# Arduino_Clock_Dividerx4_board2.net
KiCad netlist of a schematic drawn in EAGLE
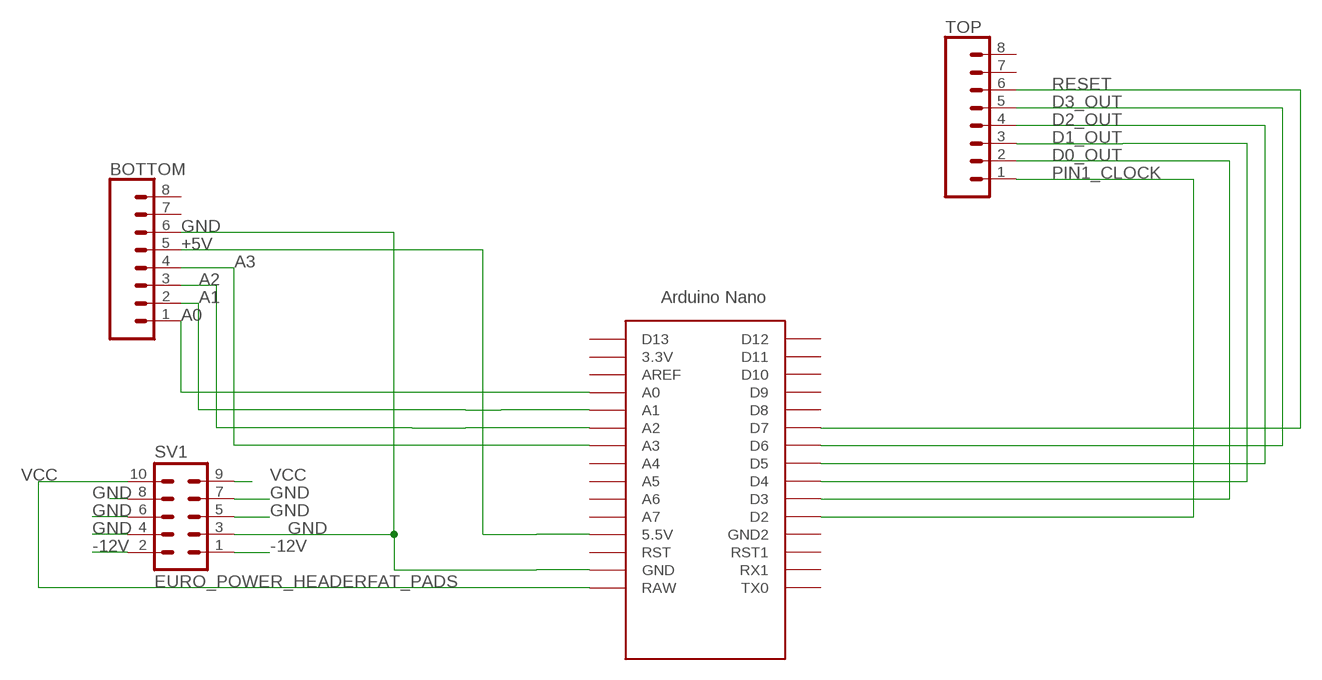
[diagram p0: schematic, sheet 1]

(export (version "E")
  (design (tool "Eeschema 10.0.6"))
  (components
    (comp (ref "BOTTOM")
      (value "CONN_08LONGPADS")
      (footprint "eagle-import:1X08_LONGPADS")
      (libsource (lib "eagle-import") (part "CONN_08LONGPADS"))
    )
    (comp (ref "SV1")
      (value "EURO_POWER_HEADERFAT_PADS")
      (footprint "eagle-import:EURO_PWR_HEADER_FAT")
      (libsource (lib "eagle-import") (part "EURO_POWER_HEADERFAT_PADS"))
    )
    (comp (ref "TOP")
      (value "CONN_08LONGPADS")
      (footprint "eagle-import:1X08_LONGPADS")
      (libsource (lib "eagle-import") (part "CONN_08LONGPADS"))
    )
    (comp (ref "U$1")
      (value "NANO")
      (footprint "eagle-import:NANO")
      (libsource (lib "eagle-import") (part "NANO"))
    )
  )
  (nets
    (net (code "1") (name "/+5V") (class "Default")
      (node (ref "BOTTOM") (pin "5") (pinfunction "5_5") (pintype "passive"))
      (node (ref "U$1") (pin "5V") (pinfunction "5.5V_5V") (pintype "bidirectional"))
    )
    (net (code "2") (name "/-12V") (class "Default")
      (node (ref "SV1") (pin "1") (pinfunction "1_1") (pintype "passive"))
      (node (ref "SV1") (pin "2") (pinfunction "2_2") (pintype "passive"))
    )
    (net (code "3") (name "/A0") (class "Default")
      (node (ref "BOTTOM") (pin "1") (pinfunction "1_1") (pintype "passive"))
      (node (ref "U$1") (pin "A0") (pinfunction "A0_A0") (pintype "bidirectional"))
    )
    (net (code "4") (name "/A1") (class "Default")
      (node (ref "BOTTOM") (pin "2") (pinfunction "2_2") (pintype "passive"))
      (node (ref "U$1") (pin "A1") (pinfunction "A1_A1") (pintype "bidirectional"))
    )
    (net (code "5") (name "/A2") (class "Default")
      (node (ref "BOTTOM") (pin "3") (pinfunction "3_3") (pintype "passive"))
      (node (ref "U$1") (pin "A2") (pinfunction "A2_A2") (pintype "bidirectional"))
    )
    (net (code "6") (name "/A3") (class "Default")
      (node (ref "BOTTOM") (pin "4") (pinfunction "4_4") (pintype "passive"))
      (node (ref "U$1") (pin "A3") (pinfunction "A3_A3") (pintype "bidirectional"))
    )
    (net (code "7") (name "/D0_OUT") (class "Default")
      (node (ref "TOP") (pin "2") (pinfunction "2_2") (pintype "passive"))
      (node (ref "U$1") (pin "D3") (pinfunction "D3_D3") (pintype "bidirectional"))
    )
    (net (code "8") (name "/D1_OUT") (class "Default")
      (node (ref "TOP") (pin "3") (pinfunction "3_3") (pintype "passive"))
      (node (ref "U$1") (pin "D4") (pinfunction "D4_D4") (pintype "bidirectional"))
    )
    (net (code "9") (name "/D2_OUT") (class "Default")
      (node (ref "TOP") (pin "4") (pinfunction "4_4") (pintype "passive"))
      (node (ref "U$1") (pin "D5") (pinfunction "D5_D5") (pintype "bidirectional"))
    )
    (net (code "10") (name "/D3_OUT") (class "Default")
      (node (ref "TOP") (pin "5") (pinfunction "5_5") (pintype "passive"))
      (node (ref "U$1") (pin "D6") (pinfunction "D6_D6") (pintype "bidirectional"))
    )
    (net (code "11") (name "/GND") (class "Default")
      (node (ref "BOTTOM") (pin "6") (pinfunction "6_6") (pintype "passive"))
      (node (ref "SV1") (pin "3") (pinfunction "3_3") (pintype "passive"))
      (node (ref "SV1") (pin "4") (pinfunction "4_4") (pintype "passive"))
      (node (ref "SV1") (pin "5") (pinfunction "5_5") (pintype "passive"))
      (node (ref "SV1") (pin "6") (pinfunction "6_6") (pintype "passive"))
      (node (ref "SV1") (pin "7") (pinfunction "7_7") (pintype "passive"))
      (node (ref "SV1") (pin "8") (pinfunction "8_8") (pintype "passive"))
      (node (ref "U$1") (pin "GND") (pinfunction "GND_GND") (pintype "bidirectional"))
    )
    (net (code "12") (name "/PIN1_CLOCK") (class "Default")
      (node (ref "TOP") (pin "1") (pinfunction "1_1") (pintype "passive"))
      (node (ref "U$1") (pin "D2") (pinfunction "D2_D2") (pintype "bidirectional"))
    )
    (net (code "13") (name "/RESET") (class "Default")
      (node (ref "TOP") (pin "6") (pinfunction "6_6") (pintype "passive"))
      (node (ref "U$1") (pin "D7") (pinfunction "D7_D7") (pintype "bidirectional"))
    )
    (net (code "14") (name "/VCC") (class "Default")
      (node (ref "SV1") (pin "10") (pinfunction "10_10") (pintype "passive"))
      (node (ref "SV1") (pin "9") (pinfunction "9_9") (pintype "passive"))
      (node (ref "U$1") (pin "RAW") (pinfunction "RAW_RAW") (pintype "bidirectional"))
    )
    (net (code "15") (name "unconnected-(BOTTOM-Pad7)") (class "Default")
      (node (ref "BOTTOM") (pin "7") (pinfunction "7_7") (pintype "passive"))
    )
    (net (code "16") (name "unconnected-(BOTTOM-Pad8)") (class "Default")
      (node (ref "BOTTOM") (pin "8") (pinfunction "8_8") (pintype "passive"))
    )
    (net (code "17") (name "unconnected-(TOP-Pad7)") (class "Default")
      (node (ref "TOP") (pin "7") (pinfunction "7_7") (pintype "passive"))
    )
    (net (code "18") (name "unconnected-(TOP-Pad8)") (class "Default")
      (node (ref "TOP") (pin "8") (pinfunction "8_8") (pintype "passive"))
    )
    (net (code "19") (name "unconnected-(U$1-GND2-PadGND1)") (class "Default")
      (node (ref "U$1") (pin "GND1") (pinfunction "GND2_GND1") (pintype "bidirectional"))
    )
    (net (code "20") (name "unconnected-(U$1-Pad3.3V)") (class "Default")
      (node (ref "U$1") (pin "3.3V") (pinfunction "3.3V_3.3V") (pintype "bidirectional"))
    )
    (net (code "21") (name "unconnected-(U$1-PadA4)") (class "Default")
      (node (ref "U$1") (pin "A4") (pinfunction "A4_A4") (pintype "bidirectional"))
    )
    (net (code "22") (name "unconnected-(U$1-PadA5)") (class "Default")
      (node (ref "U$1") (pin "A5") (pinfunction "A5_A5") (pintype "bidirectional"))
    )
    (net (code "23") (name "unconnected-(U$1-PadA6)") (class "Default")
      (node (ref "U$1") (pin "A6") (pinfunction "A6_A6") (pintype "bidirectional"))
    )
    (net (code "24") (name "unconnected-(U$1-PadA7)") (class "Default")
      (node (ref "U$1") (pin "A7") (pinfunction "A7_A7") (pintype "bidirectional"))
    )
    (net (code "25") (name "unconnected-(U$1-PadAREF)") (class "Default")
      (node (ref "U$1") (pin "AREF") (pinfunction "AREF_AREF") (pintype "bidirectional"))
    )
    (net (code "26") (name "unconnected-(U$1-PadD8)") (class "Default")
      (node (ref "U$1") (pin "D8") (pinfunction "D8_D8") (pintype "bidirectional"))
    )
    (net (code "27") (name "unconnected-(U$1-PadD9)") (class "Default")
      (node (ref "U$1") (pin "D9") (pinfunction "D9_D9") (pintype "bidirectional"))
    )
    (net (code "28") (name "unconnected-(U$1-PadD10)") (class "Default")
      (node (ref "U$1") (pin "D10") (pinfunction "D10_D10") (pintype "bidirectional"))
    )
    (net (code "29") (name "unconnected-(U$1-PadD11)") (class "Default")
      (node (ref "U$1") (pin "D11") (pinfunction "D11_D11") (pintype "bidirectional"))
    )
    (net (code "30") (name "unconnected-(U$1-PadD12)") (class "Default")
      (node (ref "U$1") (pin "D12") (pinfunction "D12_D12") (pintype "bidirectional"))
    )
    (net (code "31") (name "unconnected-(U$1-PadD13)") (class "Default")
      (node (ref "U$1") (pin "D13") (pinfunction "D13_D13") (pintype "bidirectional"))
    )
    (net (code "32") (name "unconnected-(U$1-PadRST)") (class "Default")
      (node (ref "U$1") (pin "RST") (pinfunction "RST_RST") (pintype "bidirectional"))
    )
    (net (code "33") (name "unconnected-(U$1-PadRST1)") (class "Default")
      (node (ref "U$1") (pin "RST1") (pinfunction "RST1_RST1") (pintype "bidirectional"))
    )
    (net (code "34") (name "unconnected-(U$1-PadRX1)") (class "Default")
      (node (ref "U$1") (pin "RX1") (pinfunction "RX1_RX1") (pintype "bidirectional"))
    )
    (net (code "35") (name "unconnected-(U$1-PadTX0)") (class "Default")
      (node (ref "U$1") (pin "TX0") (pinfunction "TX0_TX0") (pintype "bidirectional"))
    )
  )
)
